# STM32_DDS.net
KiCad netlist of a schematic drawn in Altium Designer
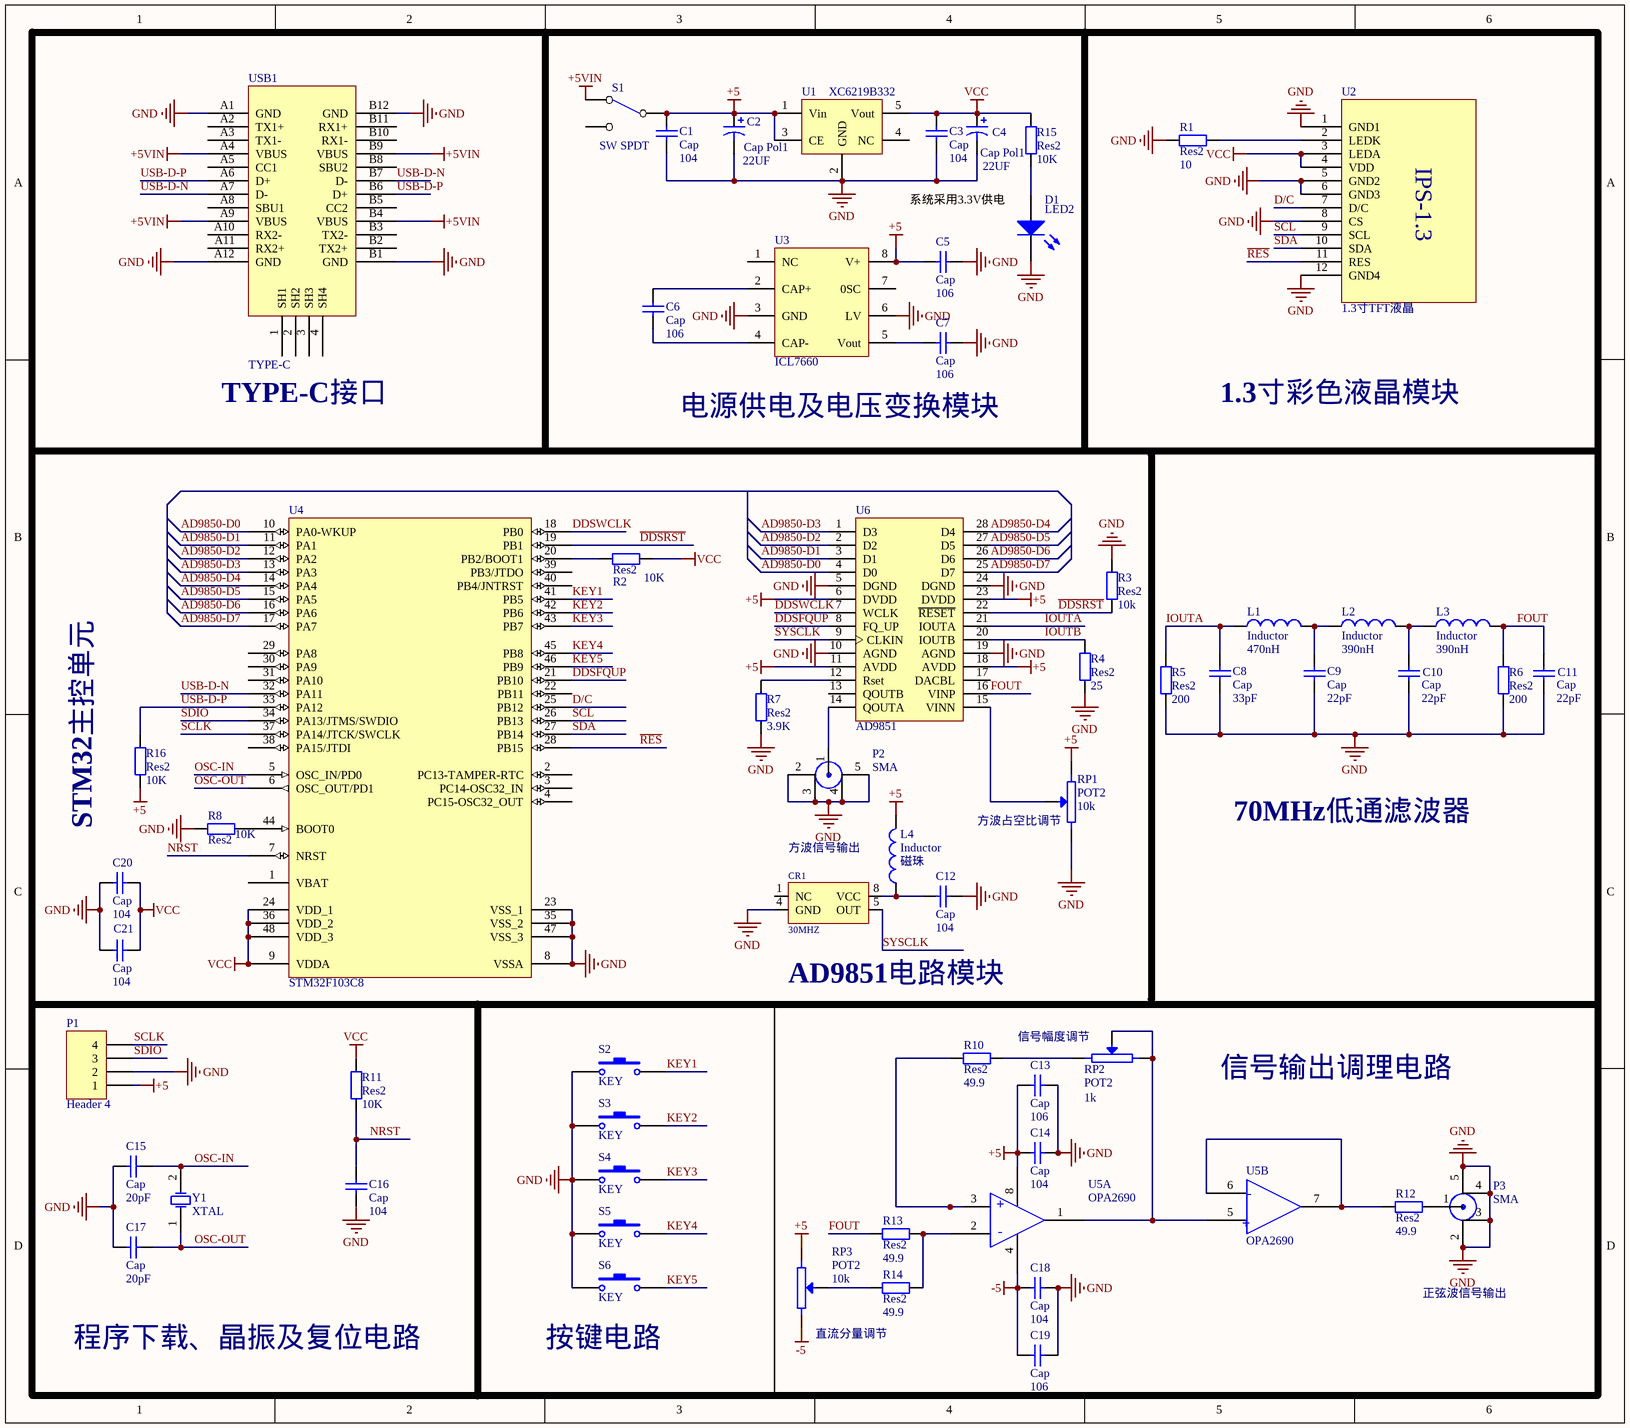
[diagram p0: 基于STM32的DDS信号源（单张）.SchDoc]

(export (version "E")
  (design (tool "Eeschema 10.0.6"))
  (components
    (comp (ref "C1")
      (value "Cap")
      (footprint "C0805")
      (description "Capacitor")
      (fields (field (name "ALTIUM_VALUE") "104") (field (name "PUBLISHER") "Altium Limited"))
      (libsource (lib "Miscellaneous Devices") (part "Cap"))
    )
    (comp (ref "C2")
      (value "Cap Pol1")
      (footprint "C1210_N")
      (description "Polarized Capacitor (Radial)")
      (fields (field (name "ALTIUM_VALUE") "22UF") (field (name "PUBLISHER") "Altium Limited"))
      (libsource (lib "Miscellaneous Devices") (part "Cap Pol1"))
    )
    (comp (ref "C3")
      (value "Cap")
      (footprint "C0805")
      (description "Capacitor")
      (fields (field (name "ALTIUM_VALUE") "104") (field (name "PUBLISHER") "Altium Limited"))
      (libsource (lib "Miscellaneous Devices") (part "Cap"))
    )
    (comp (ref "C4")
      (value "Cap Pol1")
      (footprint "C1210_N")
      (description "Polarized Capacitor (Radial)")
      (fields (field (name "ALTIUM_VALUE") "22UF") (field (name "PUBLISHER") "Altium Limited"))
      (libsource (lib "Miscellaneous Devices") (part "Cap Pol1"))
    )
    (comp (ref "C5")
      (value "Cap")
      (footprint "C0805")
      (description "Capacitor")
      (fields (field (name "ALTIUM_VALUE") "106") (field (name "PUBLISHER") "Altium Limited"))
      (libsource (lib "Miscellaneous Devices") (part "Cap"))
    )
    (comp (ref "C6")
      (value "Cap")
      (footprint "C0805")
      (description "Capacitor")
      (fields (field (name "ALTIUM_VALUE") "106") (field (name "PUBLISHER") "Altium Limited"))
      (libsource (lib "Miscellaneous Devices") (part "Cap"))
    )
    (comp (ref "C7")
      (value "Cap")
      (footprint "C0805")
      (description "Capacitor")
      (fields (field (name "ALTIUM_VALUE") "106") (field (name "PUBLISHER") "Altium Limited"))
      (libsource (lib "Miscellaneous Devices") (part "Cap"))
    )
    (comp (ref "C8")
      (value "Cap")
      (footprint "C0805")
      (description "Capacitor")
      (fields (field (name "ALTIUM_VALUE") "33pF") (field (name "PUBLISHER") "Altium Limited"))
      (libsource (lib "Miscellaneous Devices") (part "Cap"))
    )
    (comp (ref "C9")
      (value "Cap")
      (footprint "C0805")
      (description "Capacitor")
      (fields (field (name "ALTIUM_VALUE") "22pF") (field (name "PUBLISHER") "Altium Limited"))
      (libsource (lib "Miscellaneous Devices") (part "Cap"))
    )
    (comp (ref "C10")
      (value "Cap")
      (footprint "C0805")
      (description "Capacitor")
      (fields (field (name "ALTIUM_VALUE") "22pF") (field (name "PUBLISHER") "Altium Limited"))
      (libsource (lib "Miscellaneous Devices") (part "Cap"))
    )
    (comp (ref "C11")
      (value "Cap")
      (footprint "C0805")
      (description "Capacitor")
      (fields (field (name "ALTIUM_VALUE") "22pF") (field (name "PUBLISHER") "Altium Limited"))
      (libsource (lib "Miscellaneous Devices") (part "Cap"))
    )
    (comp (ref "C12")
      (value "Cap")
      (footprint "C0805")
      (description "Capacitor")
      (fields (field (name "ALTIUM_VALUE") "104") (field (name "PUBLISHER") "Altium Limited"))
      (libsource (lib "Miscellaneous Devices") (part "Cap"))
    )
    (comp (ref "C13")
      (value "Cap")
      (footprint "C0805")
      (description "Capacitor")
      (fields (field (name "ALTIUM_VALUE") "106") (field (name "PUBLISHER") "Altium Limited"))
      (libsource (lib "Miscellaneous Devices") (part "Cap"))
    )
    (comp (ref "C14")
      (value "Cap")
      (footprint "C0805")
      (description "Capacitor")
      (fields (field (name "ALTIUM_VALUE") "104") (field (name "PUBLISHER") "Altium Limited"))
      (libsource (lib "Miscellaneous Devices") (part "Cap"))
    )
    (comp (ref "C15")
      (value "Cap")
      (footprint "C0805")
      (description "Capacitor")
      (fields (field (name "ALTIUM_VALUE") "20pF") (field (name "PUBLISHER") "Altium Limited"))
      (libsource (lib "Miscellaneous Devices") (part "Cap"))
    )
    (comp (ref "C16")
      (value "Cap")
      (footprint "C0805")
      (description "Capacitor")
      (fields (field (name "ALTIUM_VALUE") "104") (field (name "PUBLISHER") "Altium Limited"))
      (libsource (lib "Miscellaneous Devices") (part "Cap"))
    )
    (comp (ref "C17")
      (value "Cap")
      (footprint "C0805")
      (description "Capacitor")
      (fields (field (name "ALTIUM_VALUE") "20pF") (field (name "PUBLISHER") "Altium Limited"))
      (libsource (lib "Miscellaneous Devices") (part "Cap"))
    )
    (comp (ref "C18")
      (value "Cap")
      (footprint "C0805")
      (description "Capacitor")
      (fields (field (name "ALTIUM_VALUE") "104") (field (name "PUBLISHER") "Altium Limited"))
      (libsource (lib "Miscellaneous Devices") (part "Cap"))
    )
    (comp (ref "C19")
      (value "Cap")
      (footprint "C0805")
      (description "Capacitor")
      (fields (field (name "ALTIUM_VALUE") "106") (field (name "PUBLISHER") "Altium Limited"))
      (libsource (lib "Miscellaneous Devices") (part "Cap"))
    )
    (comp (ref "C20")
      (value "Cap")
      (footprint "C0805")
      (description "Capacitor")
      (fields (field (name "ALTIUM_VALUE") "104") (field (name "PUBLISHER") "Altium Limited"))
      (libsource (lib "Miscellaneous Devices") (part "Cap"))
    )
    (comp (ref "C21")
      (value "Cap")
      (footprint "C0805")
      (description "Capacitor")
      (fields (field (name "ALTIUM_VALUE") "104") (field (name "PUBLISHER") "Altium Limited"))
      (libsource (lib "Miscellaneous Devices") (part "Cap"))
    )
    (comp (ref "CR1")
      (value "30MHZ")
      (footprint "CRYSTAL-SMT-5X7")
      (libsource (lib "刘涛20141105") (part "CRYSTAL-DIP8"))
    )
    (comp (ref "D1")
      (value "LED2")
      (footprint "D0805+")
      (description "Typical RED, GREEN, YELLOW, AMBER GaAs LED")
      (fields (field (name "PUBLISHER") "Altium Limited"))
      (libsource (lib "Miscellaneous Devices") (part "LED2"))
    )
    (comp (ref "L1")
      (value "Inductor")
      (footprint "6-0805_N")
      (fields (field (name "ALTIUM_VALUE") "470nH") (field (name "PUBLISHER") "Altium Limited"))
      (libsource (lib "Miscellaneous Devices") (part "Inductor"))
    )
    (comp (ref "L2")
      (value "Inductor")
      (footprint "6-0805_N")
      (fields (field (name "ALTIUM_VALUE") "390nH") (field (name "PUBLISHER") "Altium Limited"))
      (libsource (lib "Miscellaneous Devices") (part "Inductor"))
    )
    (comp (ref "L3")
      (value "Inductor")
      (footprint "6-0805_N")
      (fields (field (name "ALTIUM_VALUE") "390nH") (field (name "PUBLISHER") "Altium Limited"))
      (libsource (lib "Miscellaneous Devices") (part "Inductor"))
    )
    (comp (ref "L4")
      (value "Inductor")
      (footprint "6-0805_N")
      (fields (field (name "ALTIUM_VALUE") "磁珠") (field (name "PUBLISHER") "Altium Limited"))
      (libsource (lib "Miscellaneous Devices") (part "Inductor"))
    )
    (comp (ref "P1")
      (value "Header 4")
      (footprint "HDR1X4")
      (description "Header, 4-Pin")
      (fields (field (name "PUBLISHER") "Altium Limited"))
      (libsource (lib "Miscellaneous Connectors") (part "Header 4"))
    )
    (comp (ref "P2") (value "SMA") (footprint "SMA-KE") (libsource (lib "原理图库") (part "SMA")))
    (comp (ref "P3") (value "SMA") (footprint "SMA-KE") (libsource (lib "原理图库") (part "SMA")))
    (comp (ref "R1")
      (value "Res2")
      (footprint "6-0805_N")
      (description "Resistor")
      (fields (field (name "ALTIUM_VALUE") "10") (field (name "PUBLISHER") "Altium Limited"))
      (libsource (lib "") (part "Res2_1"))
    )
    (comp (ref "R2")
      (value "Res2")
      (footprint "6-0805_N")
      (description "Resistor")
      (fields (field (name "ALTIUM_VALUE") "10K") (field (name "PUBLISHER") "Altium Limited"))
      (libsource (lib "") (part "Res2_2"))
    )
    (comp (ref "R3")
      (value "Res2")
      (footprint "6-0805_N")
      (description "Resistor")
      (fields (field (name "ALTIUM_VALUE") "10k") (field (name "PUBLISHER") "Altium Limited"))
      (libsource (lib "Miscellaneous Devices") (part "Res2"))
    )
    (comp (ref "R4")
      (value "Res2")
      (footprint "6-0805_N")
      (description "Resistor")
      (fields (field (name "ALTIUM_VALUE") "25") (field (name "PUBLISHER") "Altium Limited"))
      (libsource (lib "Miscellaneous Devices") (part "Res2"))
    )
    (comp (ref "R5")
      (value "Res2")
      (footprint "6-0805_N")
      (description "Resistor")
      (fields (field (name "ALTIUM_VALUE") "200") (field (name "PUBLISHER") "Altium Limited"))
      (libsource (lib "Miscellaneous Devices") (part "Res2"))
    )
    (comp (ref "R6")
      (value "Res2")
      (footprint "6-0805_N")
      (description "Resistor")
      (fields (field (name "ALTIUM_VALUE") "200") (field (name "PUBLISHER") "Altium Limited"))
      (libsource (lib "Miscellaneous Devices") (part "Res2"))
    )
    (comp (ref "R7")
      (value "Res2")
      (footprint "6-0805_N")
      (description "Resistor")
      (fields (field (name "ALTIUM_VALUE") "3.9K") (field (name "PUBLISHER") "Altium Limited"))
      (libsource (lib "Miscellaneous Devices") (part "Res2"))
    )
    (comp (ref "R8")
      (value "Res2")
      (footprint "6-0805_N")
      (description "Resistor")
      (fields (field (name "ALTIUM_VALUE") "10K") (field (name "PUBLISHER") "Altium Limited"))
      (libsource (lib "") (part "Res2_2"))
    )
    (comp (ref "R10")
      (value "Res2")
      (footprint "6-0805_N")
      (description "Resistor")
      (fields (field (name "ALTIUM_VALUE") "49.9") (field (name "PUBLISHER") "Altium Limited"))
      (libsource (lib "") (part "Res2_1"))
    )
    (comp (ref "R11")
      (value "Res2")
      (footprint "6-0805_N")
      (description "Resistor")
      (fields (field (name "ALTIUM_VALUE") "10K") (field (name "PUBLISHER") "Altium Limited"))
      (libsource (lib "Miscellaneous Devices") (part "Res2"))
    )
    (comp (ref "R12")
      (value "Res2")
      (footprint "6-0805_N")
      (description "Resistor")
      (fields (field (name "ALTIUM_VALUE") "49.9") (field (name "PUBLISHER") "Altium Limited"))
      (libsource (lib "") (part "Res2_1"))
    )
    (comp (ref "R13")
      (value "Res2")
      (footprint "6-0805_N")
      (description "Resistor")
      (fields (field (name "ALTIUM_VALUE") "49.9") (field (name "PUBLISHER") "Altium Limited"))
      (libsource (lib "") (part "Res2_1"))
    )
    (comp (ref "R14")
      (value "Res2")
      (footprint "6-0805_N")
      (description "Resistor")
      (fields (field (name "ALTIUM_VALUE") "49.9") (field (name "PUBLISHER") "Altium Limited"))
      (libsource (lib "") (part "Res2_1"))
    )
    (comp (ref "R15")
      (value "Res2")
      (footprint "6-0805_N")
      (description "Resistor")
      (fields (field (name "ALTIUM_VALUE") "10K") (field (name "PUBLISHER") "Altium Limited"))
      (libsource (lib "Miscellaneous Devices") (part "Res2"))
    )
    (comp (ref "R16")
      (value "Res2")
      (footprint "6-0805_N")
      (description "Resistor")
      (fields (field (name "ALTIUM_VALUE") "10K") (field (name "PUBLISHER") "Altium Limited"))
      (libsource (lib "") (part "Res2_3"))
    )
    (comp (ref "RP1")
      (value "POT2")
      (footprint "VR7")
      (description "Potentiometer")
      (fields (field (name "ALTIUM_VALUE") "10k"))
      (libsource (lib "刘涛20181107") (part "POT2"))
    )
    (comp (ref "RP2")
      (value "POT2")
      (footprint "VR7")
      (description "Potentiometer")
      (fields (field (name "ALTIUM_VALUE") "1k"))
      (libsource (lib "刘涛20181107") (part "POT2"))
    )
    (comp (ref "RP3")
      (value "POT2")
      (footprint "VR7")
      (description "Potentiometer")
      (fields (field (name "ALTIUM_VALUE") "10k"))
      (libsource (lib "刘涛20181107") (part "POT2"))
    )
    (comp (ref "S1")
      (value "SW SPDT")
      (footprint "SW-SPDT-7P")
      (libsource (lib "刘涛20150421") (part "SW SPDT"))
    )
    (comp (ref "S2")
      (value "KEY")
      (footprint "SW-MINI")
      (description "Switch")
      (fields (field (name "PUBLISHER") "Altium Limited"))
      (libsource (lib "Miscellaneous Devices") (part "SW-PB"))
    )
    (comp (ref "S3")
      (value "KEY")
      (footprint "SW-MINI")
      (description "Switch")
      (fields (field (name "PUBLISHER") "Altium Limited"))
      (libsource (lib "Miscellaneous Devices") (part "SW-PB"))
    )
    (comp (ref "S4")
      (value "KEY")
      (footprint "SW-MINI")
      (description "Switch")
      (fields (field (name "PUBLISHER") "Altium Limited"))
      (libsource (lib "Miscellaneous Devices") (part "SW-PB"))
    )
    (comp (ref "S5")
      (value "KEY")
      (footprint "SW-MINI")
      (description "Switch")
      (fields (field (name "PUBLISHER") "Altium Limited"))
      (libsource (lib "Miscellaneous Devices") (part "SW-PB"))
    )
    (comp (ref "S6")
      (value "KEY")
      (footprint "SW-MINI")
      (description "Switch")
      (fields (field (name "PUBLISHER") "Altium Limited"))
      (libsource (lib "Miscellaneous Devices") (part "SW-PB"))
    )
    (comp (ref "U1")
      (value "XC6219B332")
      (footprint "SOT23-5L")
      (libsource (lib "刘涛20161024") (part "XC6219"))
    )
    (comp (ref "U2")
      (value "1.3寸TFT液晶")
      (footprint "1.3-TFT-TPS")
      (libsource (lib "刘涛20181107") (part "1.3寸TFT液晶"))
    )
    (comp (ref "U3") (value "ICL7660") (footprint "SO8_N") (libsource (lib "刘涛20181107") (part "ICL7660")))
    (comp (ref "U4")
      (value "STM32F103C8")
      (footprint "TQFP-48")
      (description "Flaah:64/RAM:20/IO:36")
      (fields (field (name "版权归属") "源创客"))
      (libsource (lib "2.1   - STM32系列单片机") (part "STM32F103C8"))
    )
    (comp (ref "U5") (value "OPA2690") (footprint "SO-8") (libsource (lib "原理图库") (part "OPA2690")))
    (comp (ref "U6") (value "AD9851") (footprint "TSSOP28") (libsource (lib "原理图库") (part "AD9851")))
    (comp (ref "USB1") (value "TYPE-C") (footprint "TYPE-C") (libsource (lib "Lighting") (part "TYPE-C")))
    (comp (ref "Y1")
      (value "XTAL")
      (footprint "XTAL2")
      (description "Crystal Oscillator")
      (fields (field (name "PUBLISHER") "Altium Limited"))
      (libsource (lib "Miscellaneous Devices") (part "XTAL"))
    )
  )
  (nets
    (net (code "1") (name "+5") (class "Default")
      (node (ref "C1") (pin "2") (pinfunction "2_2") (pintype "passive"))
      (node (ref "C13") (pin "2") (pinfunction "2_2") (pintype "passive"))
      (node (ref "C14") (pin "2") (pinfunction "2_2") (pintype "passive"))
      (node (ref "C2") (pin "1") (pinfunction "1_1") (pintype "passive"))
      (node (ref "C5") (pin "2") (pinfunction "2_2") (pintype "passive"))
      (node (ref "L4") (pin "2") (pinfunction "2_2") (pintype "passive"))
      (node (ref "P1") (pin "1") (pinfunction "1_1") (pintype "passive"))
      (node (ref "R16") (pin "2") (pinfunction "2_2") (pintype "passive"))
      (node (ref "RP1") (pin "2") (pinfunction "2_2") (pintype "passive"))
      (node (ref "RP3") (pin "1") (pinfunction "1_1") (pintype "passive"))
      (node (ref "S1") (pin "2") (pinfunction "COMMON_2") (pintype "passive"))
      (node (ref "U1") (pin "1") (pinfunction "Vin_1") (pintype "passive"))
      (node (ref "U1") (pin "3") (pinfunction "CE_3") (pintype "passive"))
      (node (ref "U3") (pin "8") (pinfunction "V+_8") (pintype "passive"))
      (node (ref "U5") (pin "8") (pintype "passive"))
      (node (ref "U6") (pin "11") (pinfunction "AVDD_11") (pintype "passive"))
      (node (ref "U6") (pin "18") (pinfunction "AVDD_18") (pintype "passive"))
      (node (ref "U6") (pin "23") (pinfunction "DVDD_23") (pintype "passive"))
      (node (ref "U6") (pin "6") (pinfunction "DVDD_6") (pintype "passive"))
    )
    (net (code "2") (name "+5VIN") (class "Default")
      (node (ref "S1") (pin "1") (pinfunction "NC_1") (pintype "passive"))
      (node (ref "USB1") (pin "A4") (pinfunction "VBUS_A4") (pintype "passive"))
      (node (ref "USB1") (pin "A9") (pinfunction "VBUS_A9") (pintype "passive"))
      (node (ref "USB1") (pin "B4") (pinfunction "VBUS_B4") (pintype "passive"))
      (node (ref "USB1") (pin "B9") (pinfunction "VBUS_B9") (pintype "passive"))
    )
    (net (code "3") (name "-5") (class "Default")
      (node (ref "C18") (pin "2") (pinfunction "2_2") (pintype "passive"))
      (node (ref "C19") (pin "2") (pinfunction "2_2") (pintype "passive"))
      (node (ref "RP3") (pin "2") (pinfunction "2_2") (pintype "passive"))
      (node (ref "U5") (pin "4") (pintype "passive"))
    )
    (net (code "4") (name "/AD9850-D0") (class "Default")
      (node (ref "U4") (pin "10") (pinfunction "PA0-WKUP_10") (pintype "bidirectional"))
      (node (ref "U6") (pin "4") (pinfunction "D0_4") (pintype "passive"))
    )
    (net (code "5") (name "/AD9850-D1") (class "Default")
      (node (ref "U4") (pin "11") (pinfunction "PA1_11") (pintype "bidirectional"))
      (node (ref "U6") (pin "3") (pinfunction "D1_3") (pintype "passive"))
    )
    (net (code "6") (name "/AD9850-D2") (class "Default")
      (node (ref "U4") (pin "12") (pinfunction "PA2_12") (pintype "bidirectional"))
      (node (ref "U6") (pin "2") (pinfunction "D2_2") (pintype "passive"))
    )
    (net (code "7") (name "/AD9850-D3") (class "Default")
      (node (ref "U4") (pin "13") (pinfunction "PA3_13") (pintype "bidirectional"))
      (node (ref "U6") (pin "1") (pinfunction "D3_1") (pintype "passive"))
    )
    (net (code "8") (name "/AD9850-D4") (class "Default")
      (node (ref "U4") (pin "14") (pinfunction "PA4_14") (pintype "bidirectional"))
      (node (ref "U6") (pin "28") (pinfunction "D4_28") (pintype "passive"))
    )
    (net (code "9") (name "/AD9850-D5") (class "Default")
      (node (ref "U4") (pin "15") (pinfunction "PA5_15") (pintype "bidirectional"))
      (node (ref "U6") (pin "27") (pinfunction "D5_27") (pintype "passive"))
    )
    (net (code "10") (name "/AD9850-D6") (class "Default")
      (node (ref "U4") (pin "16") (pinfunction "PA6_16") (pintype "bidirectional"))
      (node (ref "U6") (pin "26") (pinfunction "D6_26") (pintype "passive"))
    )
    (net (code "11") (name "/AD9850-D7") (class "Default")
      (node (ref "U4") (pin "17") (pinfunction "PA7_17") (pintype "bidirectional"))
      (node (ref "U6") (pin "25") (pinfunction "D7_25") (pintype "passive"))
    )
    (net (code "12") (name "/DDSFQUP") (class "Default")
      (node (ref "U4") (pin "21") (pinfunction "PB10_21") (pintype "bidirectional"))
      (node (ref "U6") (pin "8") (pinfunction "FQ_UP_8") (pintype "passive"))
    )
    (net (code "13") (name "/DDSWCLK") (class "Default")
      (node (ref "U4") (pin "18") (pinfunction "PB0_18") (pintype "bidirectional"))
      (node (ref "U6") (pin "7") (pinfunction "WCLK_7") (pintype "passive"))
    )
    (net (code "14") (name "/D{slash}C") (class "Default")
      (node (ref "U2") (pin "7") (pinfunction "D/C_7") (pintype "passive"))
      (node (ref "U4") (pin "25") (pinfunction "PB12_25") (pintype "bidirectional"))
    )
    (net (code "15") (name "/FOUT") (class "Default")
      (node (ref "C11") (pin "2") (pinfunction "2_2") (pintype "passive"))
      (node (ref "L3") (pin "2") (pinfunction "2_2") (pintype "passive"))
      (node (ref "R13") (pin "1") (pinfunction "1_1") (pintype "passive"))
      (node (ref "R6") (pin "2") (pinfunction "2_2") (pintype "passive"))
      (node (ref "U6") (pin "16") (pinfunction "VINP_16") (pintype "passive"))
    )
    (net (code "16") (name "/IOUTA") (class "Default")
      (node (ref "C8") (pin "2") (pinfunction "2_2") (pintype "passive"))
      (node (ref "L1") (pin "1") (pinfunction "1_1") (pintype "passive"))
      (node (ref "R5") (pin "2") (pinfunction "2_2") (pintype "passive"))
      (node (ref "U6") (pin "21") (pinfunction "IOUTA_21") (pintype "passive"))
    )
    (net (code "17") (name "/IOUTB") (class "Default")
      (node (ref "R4") (pin "2") (pinfunction "2_2") (pintype "passive"))
      (node (ref "U6") (pin "20") (pinfunction "IOUTB_20") (pintype "passive"))
    )
    (net (code "18") (name "/KEY1") (class "Default")
      (node (ref "S2") (pin "2") (pinfunction "2_2") (pintype "passive"))
      (node (ref "U4") (pin "41") (pinfunction "PB5_41") (pintype "bidirectional"))
    )
    (net (code "19") (name "/KEY2") (class "Default")
      (node (ref "S3") (pin "2") (pinfunction "2_2") (pintype "passive"))
      (node (ref "U4") (pin "42") (pinfunction "PB6_42") (pintype "bidirectional"))
    )
    (net (code "20") (name "/KEY3") (class "Default")
      (node (ref "S4") (pin "2") (pinfunction "2_2") (pintype "passive"))
      (node (ref "U4") (pin "43") (pinfunction "PB7_43") (pintype "bidirectional"))
    )
    (net (code "21") (name "/KEY4") (class "Default")
      (node (ref "S5") (pin "2") (pinfunction "2_2") (pintype "passive"))
      (node (ref "U4") (pin "45") (pinfunction "PB8_45") (pintype "bidirectional"))
    )
    (net (code "22") (name "/KEY5") (class "Default")
      (node (ref "S6") (pin "2") (pinfunction "2_2") (pintype "passive"))
      (node (ref "U4") (pin "46") (pinfunction "PB9_46") (pintype "bidirectional"))
    )
    (net (code "23") (name "/NRST") (class "Default")
      (node (ref "C16") (pin "2") (pinfunction "2_2") (pintype "passive"))
      (node (ref "R11") (pin "1") (pinfunction "1_1") (pintype "passive"))
      (node (ref "U4") (pin "7") (pinfunction "NRST_7") (pintype "bidirectional"))
    )
    (net (code "24") (name "/OSC-IN") (class "Default")
      (node (ref "C15") (pin "1") (pinfunction "1_1") (pintype "passive"))
      (node (ref "U4") (pin "5") (pinfunction "OSC_IN/PD0_5") (pintype "input"))
      (node (ref "Y1") (pin "2") (pinfunction "OSC2_2") (pintype "passive"))
    )
    (net (code "25") (name "/OSC-OUT") (class "Default")
      (node (ref "C17") (pin "1") (pinfunction "1_1") (pintype "passive"))
      (node (ref "U4") (pin "6") (pinfunction "OSC_OUT/PD1_6") (pintype "output"))
      (node (ref "Y1") (pin "1") (pinfunction "OSC1_1") (pintype "passive"))
    )
    (net (code "26") (name "/SCL") (class "Default")
      (node (ref "U2") (pin "9") (pinfunction "SCL_9") (pintype "passive"))
      (node (ref "U4") (pin "26") (pinfunction "PB13_26") (pintype "bidirectional"))
    )
    (net (code "27") (name "/SCLK") (class "Default")
      (node (ref "P1") (pin "4") (pinfunction "4_4") (pintype "passive"))
      (node (ref "U4") (pin "37") (pinfunction "PA14/JTCK/SWCLK_37") (pintype "bidirectional"))
    )
    (net (code "28") (name "/SDA") (class "Default")
      (node (ref "U2") (pin "10") (pinfunction "SDA_10") (pintype "passive"))
      (node (ref "U4") (pin "27") (pinfunction "PB14_27") (pintype "bidirectional"))
    )
    (net (code "29") (name "/SDIO") (class "Default")
      (node (ref "P1") (pin "3") (pinfunction "3_3") (pintype "passive"))
      (node (ref "U4") (pin "34") (pinfunction "PA13/JTMS/SWDIO_34") (pintype "bidirectional"))
    )
    (net (code "30") (name "/SYSCLK") (class "Default")
      (node (ref "CR1") (pin "5") (pinfunction "OUT_5") (pintype "passive"))
      (node (ref "U6") (pin "9") (pinfunction "CLKIN_9") (pintype "passive"))
    )
    (net (code "31") (name "/USB-D-N") (class "Default")
      (node (ref "U4") (pin "32") (pinfunction "PA11_32") (pintype "bidirectional"))
      (node (ref "USB1") (pin "A7") (pinfunction "D-_A7") (pintype "passive"))
      (node (ref "USB1") (pin "B7") (pinfunction "D-_B7") (pintype "passive"))
    )
    (net (code "32") (name "/USB-D-P") (class "Default")
      (node (ref "R16") (pin "1") (pinfunction "1_1") (pintype "passive"))
      (node (ref "U4") (pin "33") (pinfunction "PA12_33") (pintype "bidirectional"))
      (node (ref "USB1") (pin "A6") (pinfunction "D+_A6") (pintype "passive"))
      (node (ref "USB1") (pin "B6") (pinfunction "D+_B6") (pintype "passive"))
    )
    (net (code "33") (name "/~{DDSRST}") (class "Default")
      (node (ref "R3") (pin "1") (pinfunction "1_1") (pintype "passive"))
      (node (ref "U4") (pin "19") (pinfunction "PB1_19") (pintype "bidirectional"))
      (node (ref "U6") (pin "22") (pinfunction "~{RESET}_22") (pintype "passive"))
    )
    (net (code "34") (name "/~{RES}") (class "Default")
      (node (ref "U2") (pin "11") (pinfunction "RES_11") (pintype "passive"))
      (node (ref "U4") (pin "28") (pinfunction "PB15_28") (pintype "bidirectional"))
    )
    (net (code "35") (name "GND") (class "Default")
      (node (ref "C1") (pin "1") (pinfunction "1_1") (pintype "passive"))
      (node (ref "C10") (pin "1") (pinfunction "1_1") (pintype "passive"))
      (node (ref "C11") (pin "1") (pinfunction "1_1") (pintype "passive"))
      (node (ref "C12") (pin "1") (pinfunction "1_1") (pintype "passive"))
      (node (ref "C13") (pin "1") (pinfunction "1_1") (pintype "passive"))
      (node (ref "C14") (pin "1") (pinfunction "1_1") (pintype "passive"))
      (node (ref "C15") (pin "2") (pinfunction "2_2") (pintype "passive"))
      (node (ref "C16") (pin "1") (pinfunction "1_1") (pintype "passive"))
      (node (ref "C17") (pin "2") (pinfunction "2_2") (pintype "passive"))
      (node (ref "C18") (pin "1") (pinfunction "1_1") (pintype "passive"))
      (node (ref "C19") (pin "1") (pinfunction "1_1") (pintype "passive"))
      (node (ref "C2") (pin "2") (pinfunction "2_2") (pintype "passive"))
      (node (ref "C20") (pin "2") (pinfunction "2_2") (pintype "passive"))
      (node (ref "C21") (pin "2") (pinfunction "2_2") (pintype "passive"))
      (node (ref "C3") (pin "1") (pinfunction "1_1") (pintype "passive"))
      (node (ref "C4") (pin "2") (pinfunction "2_2") (pintype "passive"))
      (node (ref "C5") (pin "1") (pinfunction "1_1") (pintype "passive"))
      (node (ref "C7") (pin "1") (pinfunction "1_1") (pintype "passive"))
      (node (ref "C8") (pin "1") (pinfunction "1_1") (pintype "passive"))
      (node (ref "C9") (pin "1") (pinfunction "1_1") (pintype "passive"))
      (node (ref "CR1") (pin "4") (pinfunction "GND_4") (pintype "passive"))
      (node (ref "D1") (pin "K") (pinfunction "K_K") (pintype "passive"))
      (node (ref "P1") (pin "2") (pinfunction "2_2") (pintype "passive"))
      (node (ref "P2") (pin "2") (pintype "passive"))
      (node (ref "P2") (pin "3") (pintype "passive"))
      (node (ref "P2") (pin "4") (pintype "passive"))
      (node (ref "P2") (pin "5") (pintype "passive"))
      (node (ref "P3") (pin "2") (pintype "passive"))
      (node (ref "P3") (pin "3") (pintype "passive"))
      (node (ref "P3") (pin "4") (pintype "passive"))
      (node (ref "P3") (pin "5") (pintype "passive"))
      (node (ref "R1") (pin "1") (pinfunction "1_1") (pintype "passive"))
      (node (ref "R3") (pin "2") (pinfunction "2_2") (pintype "passive"))
      (node (ref "R4") (pin "1") (pinfunction "1_1") (pintype "passive"))
      (node (ref "R5") (pin "1") (pinfunction "1_1") (pintype "passive"))
      (node (ref "R6") (pin "1") (pinfunction "1_1") (pintype "passive"))
      (node (ref "R7") (pin "1") (pinfunction "1_1") (pintype "passive"))
      (node (ref "R8") (pin "2") (pinfunction "2_2") (pintype "passive"))
      (node (ref "RP1") (pin "1") (pinfunction "1_1") (pintype "passive"))
      (node (ref "S2") (pin "1") (pinfunction "1_1") (pintype "passive"))
      (node (ref "S3") (pin "1") (pinfunction "1_1") (pintype "passive"))
      (node (ref "S4") (pin "1") (pinfunction "1_1") (pintype "passive"))
      (node (ref "S5") (pin "1") (pinfunction "1_1") (pintype "passive"))
      (node (ref "S6") (pin "1") (pinfunction "1_1") (pintype "passive"))
      (node (ref "U1") (pin "2") (pinfunction "GND_2") (pintype "power_in"))
      (node (ref "U2") (pin "1") (pinfunction "GND1_1") (pintype "passive"))
      (node (ref "U2") (pin "12") (pinfunction "GND4_12") (pintype "passive"))
      (node (ref "U2") (pin "5") (pinfunction "GND2_5") (pintype "passive"))
      (node (ref "U2") (pin "6") (pinfunction "GND3_6") (pintype "passive"))
      (node (ref "U2") (pin "8") (pinfunction "CS_8") (pintype "passive"))
      (node (ref "U3") (pin "3") (pinfunction "GND_3") (pintype "passive"))
      (node (ref "U3") (pin "6") (pinfunction "LV_6") (pintype "passive"))
      (node (ref "U4") (pin "23") (pinfunction "VSS_1_23") (pintype "power_in"))
      (node (ref "U4") (pin "35") (pinfunction "VSS_2_35") (pintype "power_in"))
      (node (ref "U4") (pin "47") (pinfunction "VSS_3_47") (pintype "power_in"))
      (node (ref "U4") (pin "8") (pinfunction "VSSA_8") (pintype "power_in"))
      (node (ref "U6") (pin "10") (pinfunction "AGND_10") (pintype "passive"))
      (node (ref "U6") (pin "19") (pinfunction "AGND_19") (pintype "passive"))
      (node (ref "U6") (pin "24") (pinfunction "DGND_24") (pintype "passive"))
      (node (ref "U6") (pin "5") (pinfunction "DGND_5") (pintype "passive"))
      (node (ref "USB1") (pin "A1") (pinfunction "GND_A1") (pintype "passive"))
      (node (ref "USB1") (pin "A12") (pinfunction "GND_A12") (pintype "passive"))
      (node (ref "USB1") (pin "B1") (pinfunction "GND_B1") (pintype "passive"))
      (node (ref "USB1") (pin "B12") (pinfunction "GND_B12") (pintype "passive"))
    )
    (net (code "36") (name "Net-(C9-Pad2)") (class "Default")
      (node (ref "C9") (pin "2") (pinfunction "2_2") (pintype "passive"))
      (node (ref "L1") (pin "2") (pinfunction "2_2") (pintype "passive"))
      (node (ref "L2") (pin "1") (pinfunction "1_1") (pintype "passive"))
    )
    (net (code "37") (name "Net-(C10-Pad2)") (class "Default")
      (node (ref "C10") (pin "2") (pinfunction "2_2") (pintype "passive"))
      (node (ref "L2") (pin "2") (pinfunction "2_2") (pintype "passive"))
      (node (ref "L3") (pin "1") (pinfunction "1_1") (pintype "passive"))
    )
    (net (code "38") (name "Net-(CR1-VCC)") (class "Default")
      (node (ref "C12") (pin "2") (pinfunction "2_2") (pintype "passive"))
      (node (ref "CR1") (pin "8") (pinfunction "VCC_8") (pintype "passive"))
      (node (ref "L4") (pin "1") (pinfunction "1_1") (pintype "passive"))
    )
    (net (code "39") (name "Net-(D1-PadA)") (class "Default")
      (node (ref "D1") (pin "A") (pinfunction "A_A") (pintype "passive"))
      (node (ref "R15") (pin "1") (pinfunction "1_1") (pintype "passive"))
    )
    (net (code "40") (name "Net-(P3-Pad1)") (class "Default")
      (node (ref "P3") (pin "1") (pintype "passive"))
      (node (ref "R12") (pin "2") (pinfunction "2_2") (pintype "passive"))
    )
    (net (code "41") (name "Net-(R10-Pad1)") (class "Default")
      (node (ref "R10") (pin "1") (pinfunction "1_1") (pintype "passive"))
      (node (ref "U5") (pin "3") (pintype "passive"))
    )
    (net (code "42") (name "Net-(R10-Pad2)") (class "Default")
      (node (ref "R10") (pin "2") (pinfunction "2_2") (pintype "passive"))
      (node (ref "RP2") (pin "1") (pinfunction "1_1") (pintype "passive"))
    )
    (net (code "43") (name "Net-(R12-Pad1)") (class "Default")
      (node (ref "R12") (pin "1") (pinfunction "1_1") (pintype "passive"))
      (node (ref "U5") (pin "6") (pintype "passive"))
      (node (ref "U5") (pin "7") (pintype "passive"))
    )
    (net (code "44") (name "Net-(R13-Pad2)") (class "Default")
      (node (ref "R13") (pin "2") (pinfunction "2_2") (pintype "passive"))
      (node (ref "R14") (pin "2") (pinfunction "2_2") (pintype "passive"))
      (node (ref "U5") (pin "2") (pintype "passive"))
    )
    (net (code "45") (name "Net-(R14-Pad1)") (class "Default")
      (node (ref "R14") (pin "1") (pinfunction "1_1") (pintype "passive"))
      (node (ref "RP3") (pin "3") (pinfunction "3_3") (pintype "passive"))
    )
    (net (code "46") (name "Net-(RP2-Pad2)") (class "Default")
      (node (ref "RP2") (pin "2") (pinfunction "2_2") (pintype "passive"))
      (node (ref "RP2") (pin "3") (pinfunction "3_3") (pintype "passive"))
      (node (ref "U5") (pin "1") (pintype "passive"))
      (node (ref "U5") (pin "5") (pintype "passive"))
    )
    (net (code "47") (name "Net-(U2-LEDK)") (class "Default")
      (node (ref "R1") (pin "2") (pinfunction "2_2") (pintype "passive"))
      (node (ref "U2") (pin "2") (pinfunction "LEDK_2") (pintype "passive"))
    )
    (net (code "48") (name "Net-(U3-CAP+)") (class "Default")
      (node (ref "C6") (pin "1") (pinfunction "1_1") (pintype "passive"))
      (node (ref "U3") (pin "2") (pinfunction "CAP+_2") (pintype "passive"))
    )
    (net (code "49") (name "Net-(U3-CAP-)") (class "Default")
      (node (ref "C6") (pin "2") (pinfunction "2_2") (pintype "passive"))
      (node (ref "U3") (pin "4") (pinfunction "CAP-_4") (pintype "passive"))
    )
    (net (code "50") (name "Net-(U3-Vout)") (class "Default")
      (node (ref "C7") (pin "2") (pinfunction "2_2") (pintype "passive"))
      (node (ref "U3") (pin "5") (pinfunction "Vout_5") (pintype "passive"))
    )
    (net (code "51") (name "Net-(U4-BOOT0)") (class "Default")
      (node (ref "R8") (pin "1") (pinfunction "1_1") (pintype "passive"))
      (node (ref "U4") (pin "44") (pinfunction "BOOT0_44") (pintype "input"))
    )
    (net (code "52") (name "Net-(U4-PB2{slash}BOOT1)") (class "Default")
      (node (ref "R2") (pin "2") (pinfunction "2_2") (pintype "passive"))
      (node (ref "U4") (pin "20") (pinfunction "PB2/BOOT1_20") (pintype "bidirectional"))
    )
    (net (code "53") (name "Net-(U6-QOUTA)") (class "Default")
      (node (ref "P2") (pin "1") (pintype "passive"))
      (node (ref "U6") (pin "14") (pinfunction "QOUTA_14") (pintype "passive"))
    )
    (net (code "54") (name "Net-(U6-Rset)") (class "Default")
      (node (ref "R7") (pin "2") (pinfunction "2_2") (pintype "passive"))
      (node (ref "U6") (pin "12") (pinfunction "Rset_12") (pintype "passive"))
    )
    (net (code "55") (name "Net-(U6-VINN)") (class "Default")
      (node (ref "RP1") (pin "3") (pinfunction "3_3") (pintype "passive"))
      (node (ref "U6") (pin "15") (pinfunction "VINN_15") (pintype "passive"))
    )
    (net (code "56") (name "VCC") (class "Default")
      (node (ref "C20") (pin "1") (pinfunction "1_1") (pintype "passive"))
      (node (ref "C21") (pin "1") (pinfunction "1_1") (pintype "passive"))
      (node (ref "C3") (pin "2") (pinfunction "2_2") (pintype "passive"))
      (node (ref "C4") (pin "1") (pinfunction "1_1") (pintype "passive"))
      (node (ref "R11") (pin "2") (pinfunction "2_2") (pintype "passive"))
      (node (ref "R15") (pin "2") (pinfunction "2_2") (pintype "passive"))
      (node (ref "R2") (pin "1") (pinfunction "1_1") (pintype "passive"))
      (node (ref "U1") (pin "5") (pinfunction "Vout_5") (pintype "passive"))
      (node (ref "U2") (pin "3") (pinfunction "LEDA_3") (pintype "passive"))
      (node (ref "U2") (pin "4") (pinfunction "VDD_4") (pintype "passive"))
      (node (ref "U4") (pin "24") (pinfunction "VDD_1_24") (pintype "power_in"))
      (node (ref "U4") (pin "36") (pinfunction "VDD_2_36") (pintype "power_in"))
      (node (ref "U4") (pin "48") (pinfunction "VDD_3_48") (pintype "power_in"))
      (node (ref "U4") (pin "9") (pinfunction "VDDA_9") (pintype "power_in"))
    )
    (net (code "57") (name "unconnected-(CR1-NC-Pad1)") (class "Default")
      (node (ref "CR1") (pin "1") (pinfunction "NC_1") (pintype "passive"))
    )
    (net (code "58") (name "unconnected-(S1-NO-Pad3)") (class "Default")
      (node (ref "S1") (pin "3") (pinfunction "NO_3") (pintype "passive"))
    )
    (net (code "59") (name "unconnected-(U1-NC-Pad4)") (class "Default")
      (node (ref "U1") (pin "4") (pinfunction "NC_4") (pintype "passive"))
    )
    (net (code "60") (name "unconnected-(U3-0SC-Pad7)") (class "Default")
      (node (ref "U3") (pin "7") (pinfunction "0SC_7") (pintype "passive"))
    )
    (net (code "61") (name "unconnected-(U3-NC-Pad1)") (class "Default")
      (node (ref "U3") (pin "1") (pinfunction "NC_1") (pintype "passive"))
    )
    (net (code "62") (name "unconnected-(U4-PA8-Pad29)") (class "Default")
      (node (ref "U4") (pin "29") (pinfunction "PA8_29") (pintype "bidirectional"))
    )
    (net (code "63") (name "unconnected-(U4-PA9-Pad30)") (class "Default")
      (node (ref "U4") (pin "30") (pinfunction "PA9_30") (pintype "bidirectional"))
    )
    (net (code "64") (name "unconnected-(U4-PA10-Pad31)") (class "Default")
      (node (ref "U4") (pin "31") (pinfunction "PA10_31") (pintype "bidirectional"))
    )
    (net (code "65") (name "unconnected-(U4-PA15{slash}JTDI-Pad38)") (class "Default")
      (node (ref "U4") (pin "38") (pinfunction "PA15/JTDI_38") (pintype "bidirectional"))
    )
    (net (code "66") (name "unconnected-(U4-PB3{slash}JTDO-Pad39)") (class "Default")
      (node (ref "U4") (pin "39") (pinfunction "PB3/JTDO_39") (pintype "bidirectional"))
    )
    (net (code "67") (name "unconnected-(U4-PB4{slash}JNTRST-Pad40)") (class "Default")
      (node (ref "U4") (pin "40") (pinfunction "PB4/JNTRST_40") (pintype "bidirectional"))
    )
    (net (code "68") (name "unconnected-(U4-PB11-Pad22)") (class "Default")
      (node (ref "U4") (pin "22") (pinfunction "PB11_22") (pintype "bidirectional"))
    )
    (net (code "69") (name "unconnected-(U4-PC13-TAMPER-RTC-Pad2)") (class "Default")
      (node (ref "U4") (pin "2") (pinfunction "PC13-TAMPER-RTC_2") (pintype "bidirectional"))
    )
    (net (code "70") (name "unconnected-(U4-PC14-OSC32_IN-Pad3)") (class "Default")
      (node (ref "U4") (pin "3") (pinfunction "PC14-OSC32_IN_3") (pintype "bidirectional"))
    )
    (net (code "71") (name "unconnected-(U4-PC15-OSC32_OUT-Pad4)") (class "Default")
      (node (ref "U4") (pin "4") (pinfunction "PC15-OSC32_OUT_4") (pintype "bidirectional"))
    )
    (net (code "72") (name "unconnected-(U4-VBAT-Pad1)") (class "Default")
      (node (ref "U4") (pin "1") (pinfunction "VBAT_1") (pintype "power_in"))
    )
    (net (code "73") (name "unconnected-(U6-DACBL-Pad17)") (class "Default")
      (node (ref "U6") (pin "17") (pinfunction "DACBL_17") (pintype "passive"))
    )
    (net (code "74") (name "unconnected-(U6-QOUTB-Pad13)") (class "Default")
      (node (ref "U6") (pin "13") (pinfunction "QOUTB_13") (pintype "passive"))
    )
    (net (code "75") (name "unconnected-(USB1-CC1-PadA5)") (class "Default")
      (node (ref "USB1") (pin "A5") (pinfunction "CC1_A5") (pintype "passive"))
    )
    (net (code "76") (name "unconnected-(USB1-CC2-PadB5)") (class "Default")
      (node (ref "USB1") (pin "B5") (pinfunction "CC2_B5") (pintype "passive"))
    )
    (net (code "77") (name "unconnected-(USB1-RX1+-PadB11)") (class "Default")
      (node (ref "USB1") (pin "B11") (pinfunction "RX1+_B11") (pintype "passive"))
    )
    (net (code "78") (name "unconnected-(USB1-RX1--PadB10)") (class "Default")
      (node (ref "USB1") (pin "B10") (pinfunction "RX1-_B10") (pintype "passive"))
    )
    (net (code "79") (name "unconnected-(USB1-RX2+-PadA11)") (class "Default")
      (node (ref "USB1") (pin "A11") (pinfunction "RX2+_A11") (pintype "passive"))
    )
    (net (code "80") (name "unconnected-(USB1-RX2--PadA10)") (class "Default")
      (node (ref "USB1") (pin "A10") (pinfunction "RX2-_A10") (pintype "passive"))
    )
    (net (code "81") (name "unconnected-(USB1-SBU1-PadA8)") (class "Default")
      (node (ref "USB1") (pin "A8") (pinfunction "SBU1_A8") (pintype "passive"))
    )
    (net (code "82") (name "unconnected-(USB1-SBU2-PadB8)") (class "Default")
      (node (ref "USB1") (pin "B8") (pinfunction "SBU2_B8") (pintype "passive"))
    )
    (net (code "83") (name "unconnected-(USB1-SH1-Pad1)") (class "Default")
      (node (ref "USB1") (pin "1") (pinfunction "SH1_1") (pintype "passive"))
    )
    (net (code "84") (name "unconnected-(USB1-SH2-Pad2)") (class "Default")
      (node (ref "USB1") (pin "2") (pinfunction "SH2_2") (pintype "passive"))
    )
    (net (code "85") (name "unconnected-(USB1-SH3-Pad3)") (class "Default")
      (node (ref "USB1") (pin "3") (pinfunction "SH3_3") (pintype "passive"))
    )
    (net (code "86") (name "unconnected-(USB1-SH4-Pad4)") (class "Default")
      (node (ref "USB1") (pin "4") (pinfunction "SH4_4") (pintype "passive"))
    )
    (net (code "87") (name "unconnected-(USB1-TX1+-PadA2)") (class "Default")
      (node (ref "USB1") (pin "A2") (pinfunction "TX1+_A2") (pintype "passive"))
    )
    (net (code "88") (name "unconnected-(USB1-TX1--PadA3)") (class "Default")
      (node (ref "USB1") (pin "A3") (pinfunction "TX1-_A3") (pintype "passive"))
    )
    (net (code "89") (name "unconnected-(USB1-TX2+-PadB2)") (class "Default")
      (node (ref "USB1") (pin "B2") (pinfunction "TX2+_B2") (pintype "passive"))
    )
    (net (code "90") (name "unconnected-(USB1-TX2--PadB3)") (class "Default")
      (node (ref "USB1") (pin "B3") (pinfunction "TX2-_B3") (pintype "passive"))
    )
  )
)
